# rfid_ctl.net
KiCad netlist of a schematic drawn in EAGLE
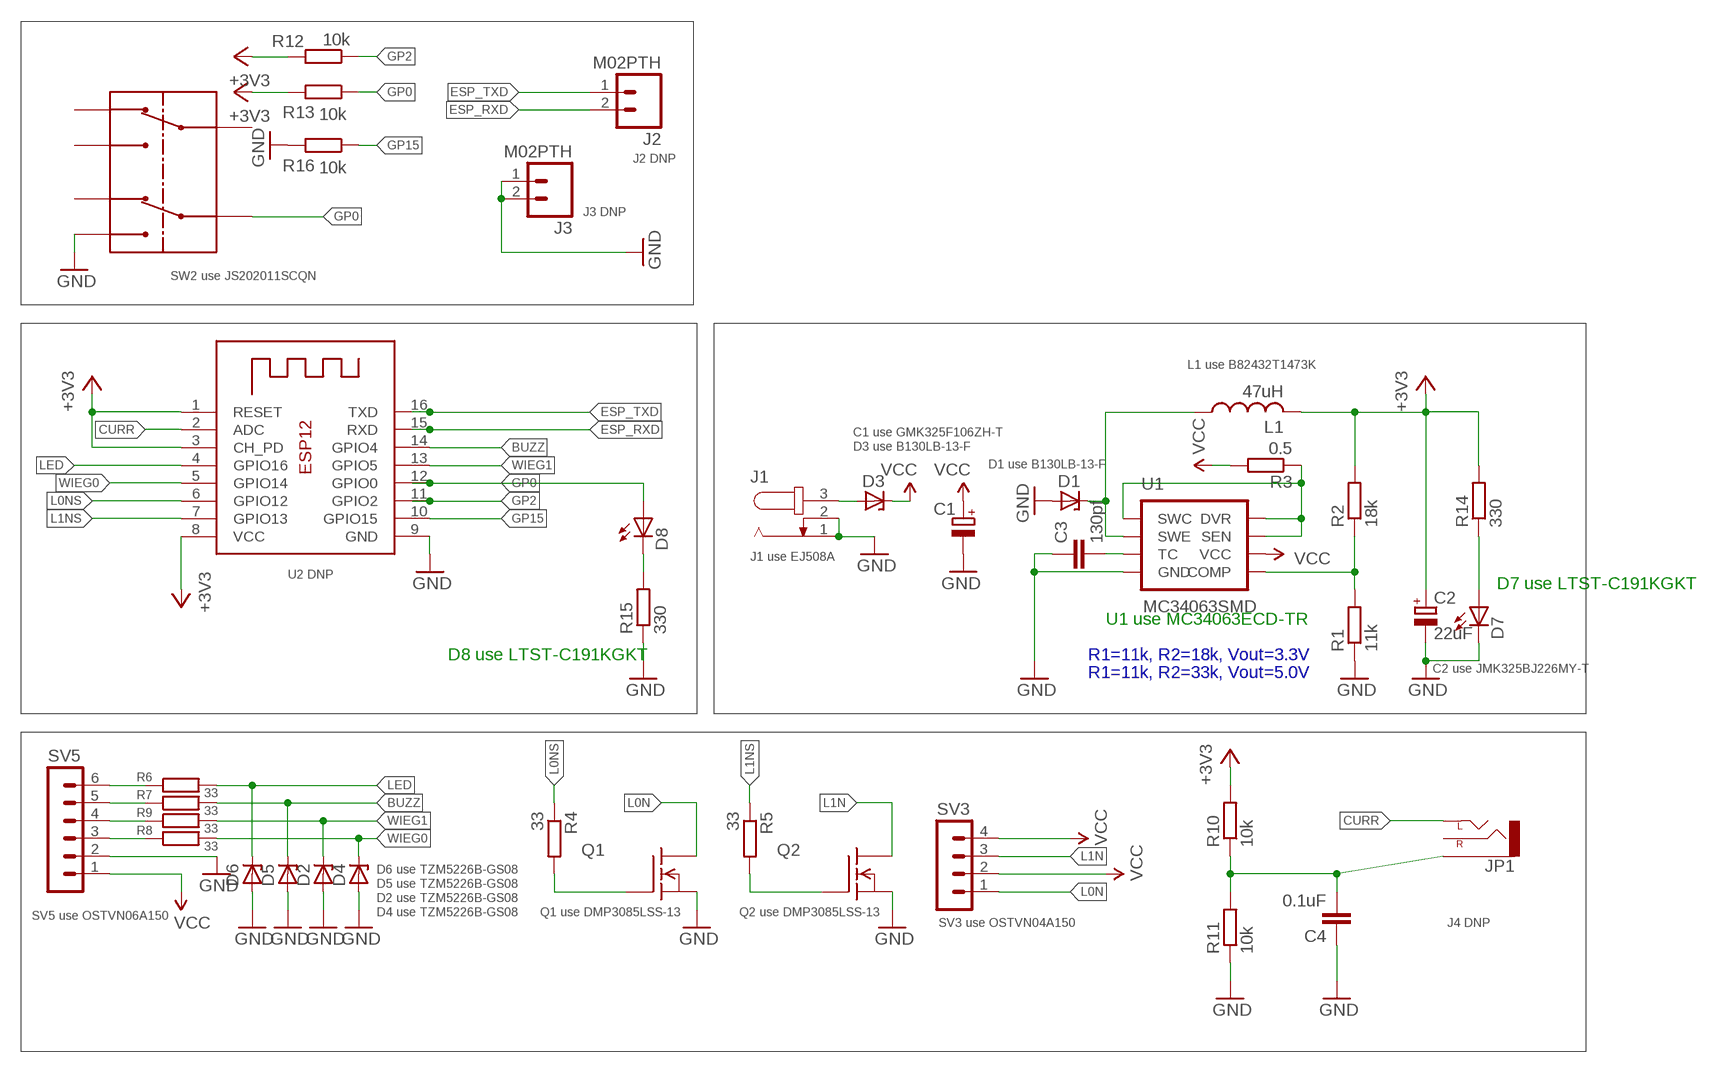
[diagram p0: schematic, sheet 1]

(export (version "E")
  (design (tool "Eeschema 10.0.6"))
  (components
    (comp (ref "C1")
      (value "CPOL-EUB/3528-21R")
      (footprint "eagle-import:B_3528-21R")
      (libsource (lib "eagle-import") (part "CPOL-EUB/3528-21R"))
    )
    (comp (ref "C2")
      (value "22uF")
      (footprint "eagle-import:B_3528-21R")
      (libsource (lib "eagle-import") (part "CPOL-EUB/3528-21R"))
    )
    (comp (ref "C3")
      (value "130pf")
      (footprint "eagle-import:C0603")
      (libsource (lib "eagle-import") (part "C-EUC0603"))
    )
    (comp (ref "C4")
      (value "0.1uF")
      (footprint "eagle-import:C0603")
      (libsource (lib "eagle-import") (part "C-EUC0603"))
    )
    (comp (ref "D1")
      (value "ZENER-DIODESMB")
      (footprint "eagle-import:SMB")
      (libsource (lib "eagle-import") (part "ZENER-DIODESMB"))
    )
    (comp (ref "D2")
      (value "ZENER-DIODESOD80C")
      (footprint "eagle-import:SOD80C")
      (libsource (lib "eagle-import") (part "ZENER-DIODESOD80C"))
    )
    (comp (ref "D3")
      (value "ZENER-DIODESMB")
      (footprint "eagle-import:SMB")
      (libsource (lib "eagle-import") (part "ZENER-DIODESMB"))
    )
    (comp (ref "D4")
      (value "ZENER-DIODESOD80C")
      (footprint "eagle-import:SOD80C")
      (libsource (lib "eagle-import") (part "ZENER-DIODESOD80C"))
    )
    (comp (ref "D5")
      (value "ZENER-DIODESOD80C")
      (footprint "eagle-import:SOD80C")
      (libsource (lib "eagle-import") (part "ZENER-DIODESOD80C"))
    )
    (comp (ref "D6")
      (value "ZENER-DIODESOD80C")
      (footprint "eagle-import:SOD80C")
      (libsource (lib "eagle-import") (part "ZENER-DIODESOD80C"))
    )
    (comp (ref "D7")
      (value "LEDCHIP-LED0603")
      (footprint "eagle-import:CHIP-LED0603")
      (libsource (lib "eagle-import") (part "LEDCHIP-LED0603"))
    )
    (comp (ref "D8")
      (value "LEDCHIP-LED0603")
      (footprint "eagle-import:CHIP-LED0603")
      (libsource (lib "eagle-import") (part "LEDCHIP-LED0603"))
    )
    (comp (ref "J1")
      (value "JACK-PLUG0")
      (footprint "eagle-import:SPC4077")
      (libsource (lib "eagle-import") (part "JACK-PLUG0"))
    )
    (comp (ref "J2")
      (value "M02PTH")
      (footprint "eagle-import:1X02")
      (libsource (lib "eagle-import") (part "M02PTH"))
    )
    (comp (ref "J3")
      (value "M02PTH")
      (footprint "eagle-import:1X02")
      (libsource (lib "eagle-import") (part "M02PTH"))
    )
    (comp (ref "JP1")
      (value "AUDIO-JACKSMD2")
      (footprint "eagle-import:AUDIO-JACK-3.5MM-SMD")
      (libsource (lib "eagle-import") (part "AUDIO-JACKSMD2"))
    )
    (comp (ref "L1")
      (value "47uH")
      (footprint "eagle-import:L1812")
      (libsource (lib "eagle-import") (part "L-USL1812"))
    )
    (comp (ref "Q1")
      (value "FDS5680")
      (footprint "eagle-import:SO-8")
      (libsource (lib "eagle-import") (part "FDS5680"))
    )
    (comp (ref "Q2")
      (value "FDS5680")
      (footprint "eagle-import:SO-8")
      (libsource (lib "eagle-import") (part "FDS5680"))
    )
    (comp (ref "R1")
      (value "11k")
      (footprint "eagle-import:R0603")
      (libsource (lib "eagle-import") (part "R-EU_R0603"))
    )
    (comp (ref "R2")
      (value "18k")
      (footprint "eagle-import:R0603")
      (libsource (lib "eagle-import") (part "R-EU_R0603"))
    )
    (comp (ref "R3")
      (value "0.5")
      (footprint "eagle-import:R0603")
      (libsource (lib "eagle-import") (part "R-EU_R0603"))
    )
    (comp (ref "R4")
      (value "33")
      (footprint "eagle-import:R0603")
      (libsource (lib "eagle-import") (part "R-EU_R0603"))
    )
    (comp (ref "R5")
      (value "33")
      (footprint "eagle-import:R0603")
      (libsource (lib "eagle-import") (part "R-EU_R0603"))
    )
    (comp (ref "R6")
      (value "33")
      (footprint "eagle-import:R0603")
      (libsource (lib "eagle-import") (part "R-EU_R0603"))
    )
    (comp (ref "R7")
      (value "33")
      (footprint "eagle-import:R0603")
      (libsource (lib "eagle-import") (part "R-EU_R0603"))
    )
    (comp (ref "R8")
      (value "33")
      (footprint "eagle-import:R0603")
      (libsource (lib "eagle-import") (part "R-EU_R0603"))
    )
    (comp (ref "R9")
      (value "33")
      (footprint "eagle-import:R0603")
      (libsource (lib "eagle-import") (part "R-EU_R0603"))
    )
    (comp (ref "R10")
      (value "10k")
      (footprint "eagle-import:R0603")
      (libsource (lib "eagle-import") (part "R-EU_R0603"))
    )
    (comp (ref "R11")
      (value "10k")
      (footprint "eagle-import:R0603")
      (libsource (lib "eagle-import") (part "R-EU_R0603"))
    )
    (comp (ref "R12")
      (value "10k")
      (footprint "eagle-import:R0603")
      (libsource (lib "eagle-import") (part "R-EU_R0603"))
    )
    (comp (ref "R13")
      (value "10k")
      (footprint "eagle-import:R0603")
      (libsource (lib "eagle-import") (part "R-EU_R0603"))
    )
    (comp (ref "R14")
      (value "330")
      (footprint "eagle-import:R0603")
      (libsource (lib "eagle-import") (part "R-EU_R0603"))
    )
    (comp (ref "R15")
      (value "330")
      (footprint "eagle-import:R0603")
      (libsource (lib "eagle-import") (part "R-EU_R0603"))
    )
    (comp (ref "R16")
      (value "10k")
      (footprint "eagle-import:R0603")
      (libsource (lib "eagle-import") (part "R-EU_R0603"))
    )
    (comp (ref "SV3")
      (value "MA04-1")
      (footprint "eagle-import:MA04-1")
      (libsource (lib "eagle-import") (part "MA04-1"))
    )
    (comp (ref "SV5")
      (value "MA06-1")
      (footprint "eagle-import:MA06-1")
      (libsource (lib "eagle-import") (part "MA06-1"))
    )
    (comp (ref "SW2")
      (value "L202011MS02Q")
      (footprint "eagle-import:SMT")
      (libsource (lib "eagle-import") (part "L202011MS02Q"))
    )
    (comp (ref "U1")
      (value "MC34063SMD")
      (footprint "eagle-import:SO08")
      (libsource (lib "eagle-import") (part "MC34063SMD"))
    )
    (comp (ref "U2")
      (value "ESP-12")
      (footprint "eagle-import:ESP-12")
      (libsource (lib "eagle-import") (part "ESP-12"))
    )
  )
  (nets
    (net (code "1") (name "+3V3") (class "Default")
      (node (ref "C2") (pin "+") (pinfunction "+_+") (pintype "passive"))
      (node (ref "L1") (pin "2") (pinfunction "2_2") (pintype "passive"))
      (node (ref "R10") (pin "2") (pinfunction "2_2") (pintype "passive"))
      (node (ref "R12") (pin "2") (pinfunction "2_2") (pintype "passive"))
      (node (ref "R13") (pin "2") (pinfunction "2_2") (pintype "passive"))
      (node (ref "R14") (pin "2") (pinfunction "2_2") (pintype "passive"))
      (node (ref "R2") (pin "2") (pinfunction "2_2") (pintype "passive"))
      (node (ref "U2") (pin "1") (pinfunction "RESET_1") (pintype "input"))
      (node (ref "U2") (pin "3") (pinfunction "CH_PD_3") (pintype "input"))
      (node (ref "U2") (pin "8") (pinfunction "VCC_8") (pintype "power_in"))
    )
    (net (code "2") (name "BUZZ") (class "Default")
      (node (ref "D5") (pin "C") (pinfunction "C_C") (pintype "passive"))
      (node (ref "R7") (pin "2") (pinfunction "2_2") (pintype "passive"))
      (node (ref "U2") (pin "14") (pinfunction "GPIO4_14") (pintype "bidirectional"))
    )
    (net (code "3") (name "CURR") (class "Default")
      (node (ref "JP1") (pin "TIP") (pinfunction "LEFT_TIP") (pintype "bidirectional"))
      (node (ref "U2") (pin "2") (pinfunction "ADC_2") (pintype "passive"))
    )
    (net (code "4") (name "ESP_RXD") (class "Default")
      (node (ref "J2") (pin "2") (pinfunction "2_2") (pintype "passive"))
      (node (ref "U2") (pin "15") (pinfunction "RXD_15") (pintype "input"))
    )
    (net (code "5") (name "ESP_TXD") (class "Default")
      (node (ref "J2") (pin "1") (pinfunction "1_1") (pintype "passive"))
      (node (ref "U2") (pin "16") (pinfunction "TXD_16") (pintype "output"))
    )
    (net (code "6") (name "GND") (class "Default")
      (node (ref "C1") (pin "-") (pinfunction "-_-") (pintype "passive"))
      (node (ref "C2") (pin "-") (pinfunction "-_-") (pintype "passive"))
      (node (ref "C3") (pin "1") (pinfunction "1_1") (pintype "passive"))
      (node (ref "C4") (pin "1") (pinfunction "1_1") (pintype "passive"))
      (node (ref "D1") (pin "A") (pinfunction "A_A") (pintype "passive"))
      (node (ref "D2") (pin "A") (pinfunction "A_A") (pintype "passive"))
      (node (ref "D4") (pin "A") (pinfunction "A_A") (pintype "passive"))
      (node (ref "D5") (pin "A") (pinfunction "A_A") (pintype "passive"))
      (node (ref "D6") (pin "A") (pinfunction "A_A") (pintype "passive"))
      (node (ref "D7") (pin "C") (pinfunction "C_C") (pintype "passive"))
      (node (ref "J1") (pin "1") (pinfunction "1_1") (pintype "passive"))
      (node (ref "J1") (pin "2") (pinfunction "2_2") (pintype "passive"))
      (node (ref "J3") (pin "1") (pinfunction "1_1") (pintype "passive"))
      (node (ref "J3") (pin "2") (pinfunction "2_2") (pintype "passive"))
      (node (ref "Q1") (pin "1") (pinfunction "S_1") (pintype "passive"))
      (node (ref "Q1") (pin "2") (pinfunction "S_2") (pintype "passive"))
      (node (ref "Q1") (pin "3") (pinfunction "S_3") (pintype "passive"))
      (node (ref "Q2") (pin "1") (pinfunction "S_1") (pintype "passive"))
      (node (ref "Q2") (pin "2") (pinfunction "S_2") (pintype "passive"))
      (node (ref "Q2") (pin "3") (pinfunction "S_3") (pintype "passive"))
      (node (ref "R1") (pin "1") (pinfunction "1_1") (pintype "passive"))
      (node (ref "R11") (pin "1") (pinfunction "1_1") (pintype "passive"))
      (node (ref "R15") (pin "1") (pinfunction "1_1") (pintype "passive"))
      (node (ref "R16") (pin "2") (pinfunction "2_2") (pintype "passive"))
      (node (ref "SV5") (pin "2") (pinfunction "2_2") (pintype "passive"))
      (node (ref "SW2") (pin "B1") (pinfunction "B1_B1") (pintype "bidirectional"))
      (node (ref "U1") (pin "4") (pinfunction "GND_4") (pintype "bidirectional"))
      (node (ref "U2") (pin "9") (pinfunction "GND_9") (pintype "power_in"))
    )
    (net (code "7") (name "GP0") (class "Default")
      (node (ref "D8") (pin "A") (pinfunction "A_A") (pintype "passive"))
      (node (ref "R13") (pin "1") (pinfunction "1_1") (pintype "passive"))
      (node (ref "SW2") (pin "B") (pinfunction "B_B") (pintype "bidirectional"))
      (node (ref "U2") (pin "12") (pinfunction "GPIO0_12") (pintype "bidirectional"))
    )
    (net (code "8") (name "GP2") (class "Default")
      (node (ref "R12") (pin "1") (pinfunction "1_1") (pintype "passive"))
      (node (ref "U2") (pin "11") (pinfunction "GPIO2_11") (pintype "bidirectional"))
    )
    (net (code "9") (name "GP15") (class "Default")
      (node (ref "R16") (pin "1") (pinfunction "1_1") (pintype "passive"))
      (node (ref "U2") (pin "10") (pinfunction "GPIO15_10") (pintype "bidirectional"))
    )
    (net (code "10") (name "L0N") (class "Default")
      (node (ref "Q1") (pin "5") (pinfunction "D_5") (pintype "passive"))
      (node (ref "Q1") (pin "6") (pinfunction "D_6") (pintype "passive"))
      (node (ref "Q1") (pin "7") (pinfunction "D_7") (pintype "passive"))
      (node (ref "Q1") (pin "8") (pinfunction "D_8") (pintype "passive"))
      (node (ref "SV3") (pin "1") (pinfunction "1_1") (pintype "passive"))
    )
    (net (code "11") (name "L0NS") (class "Default")
      (node (ref "R4") (pin "1") (pinfunction "1_1") (pintype "passive"))
      (node (ref "U2") (pin "6") (pinfunction "GPIO12_6") (pintype "bidirectional"))
    )
    (net (code "12") (name "L1N") (class "Default")
      (node (ref "Q2") (pin "5") (pinfunction "D_5") (pintype "passive"))
      (node (ref "Q2") (pin "6") (pinfunction "D_6") (pintype "passive"))
      (node (ref "Q2") (pin "7") (pinfunction "D_7") (pintype "passive"))
      (node (ref "Q2") (pin "8") (pinfunction "D_8") (pintype "passive"))
      (node (ref "SV3") (pin "3") (pinfunction "3_3") (pintype "passive"))
    )
    (net (code "13") (name "L1NS") (class "Default")
      (node (ref "R5") (pin "1") (pinfunction "1_1") (pintype "passive"))
      (node (ref "U2") (pin "7") (pinfunction "GPIO13_7") (pintype "bidirectional"))
    )
    (net (code "14") (name "LED") (class "Default")
      (node (ref "D6") (pin "C") (pinfunction "C_C") (pintype "passive"))
      (node (ref "R6") (pin "2") (pinfunction "2_2") (pintype "passive"))
      (node (ref "U2") (pin "4") (pinfunction "GPIO16_4") (pintype "bidirectional"))
    )
    (net (code "15") (name "Net-(C4-Pad2)") (class "Default")
      (node (ref "C4") (pin "2") (pinfunction "2_2") (pintype "passive"))
      (node (ref "JP1") (pin "SLEEVE") (pinfunction "SLEEVE_SLEEVE") (pintype "bidirectional"))
      (node (ref "R10") (pin "1") (pinfunction "1_1") (pintype "passive"))
      (node (ref "R11") (pin "2") (pinfunction "2_2") (pintype "passive"))
    )
    (net (code "16") (name "Net-(D3-PadA)") (class "Default")
      (node (ref "D3") (pin "A") (pinfunction "A_A") (pintype "passive"))
      (node (ref "J1") (pin "3") (pinfunction "3_3") (pintype "passive"))
    )
    (net (code "17") (name "Net-(D7-PadA)") (class "Default")
      (node (ref "D7") (pin "A") (pinfunction "A_A") (pintype "passive"))
      (node (ref "R14") (pin "1") (pinfunction "1_1") (pintype "passive"))
    )
    (net (code "18") (name "Net-(D8-PadC)") (class "Default")
      (node (ref "D8") (pin "C") (pinfunction "C_C") (pintype "passive"))
      (node (ref "R15") (pin "2") (pinfunction "2_2") (pintype "passive"))
    )
    (net (code "19") (name "Net-(Q1-G)") (class "Default")
      (node (ref "Q1") (pin "4") (pinfunction "G_4") (pintype "passive"))
      (node (ref "R4") (pin "2") (pinfunction "2_2") (pintype "passive"))
    )
    (net (code "20") (name "Net-(Q2-G)") (class "Default")
      (node (ref "Q2") (pin "4") (pinfunction "G_4") (pintype "passive"))
      (node (ref "R5") (pin "2") (pinfunction "2_2") (pintype "passive"))
    )
    (net (code "21") (name "Net-(R6-Pad1)") (class "Default")
      (node (ref "R6") (pin "1") (pinfunction "1_1") (pintype "passive"))
      (node (ref "SV5") (pin "6") (pinfunction "6_6") (pintype "passive"))
    )
    (net (code "22") (name "Net-(R7-Pad1)") (class "Default")
      (node (ref "R7") (pin "1") (pinfunction "1_1") (pintype "passive"))
      (node (ref "SV5") (pin "5") (pinfunction "5_5") (pintype "passive"))
    )
    (net (code "23") (name "Net-(R8-Pad1)") (class "Default")
      (node (ref "R8") (pin "1") (pinfunction "1_1") (pintype "passive"))
      (node (ref "SV5") (pin "4") (pinfunction "4_4") (pintype "passive"))
    )
    (net (code "24") (name "Net-(R9-Pad1)") (class "Default")
      (node (ref "R9") (pin "1") (pinfunction "1_1") (pintype "passive"))
      (node (ref "SV5") (pin "3") (pinfunction "3_3") (pintype "passive"))
    )
    (net (code "25") (name "Net-(U1-COMP)") (class "Default")
      (node (ref "R1") (pin "2") (pinfunction "2_2") (pintype "passive"))
      (node (ref "R2") (pin "1") (pinfunction "1_1") (pintype "passive"))
      (node (ref "U1") (pin "5") (pinfunction "COMP_5") (pintype "bidirectional"))
    )
    (net (code "26") (name "Net-(U1-DVR)") (class "Default")
      (node (ref "R3") (pin "1") (pinfunction "1_1") (pintype "passive"))
      (node (ref "U1") (pin "1") (pinfunction "SWC_1") (pintype "bidirectional"))
      (node (ref "U1") (pin "7") (pinfunction "SEN_7") (pintype "bidirectional"))
      (node (ref "U1") (pin "8") (pinfunction "DVR_8") (pintype "bidirectional"))
    )
    (net (code "27") (name "Net-(U1-SWE)") (class "Default")
      (node (ref "D1") (pin "C") (pinfunction "C_C") (pintype "passive"))
      (node (ref "L1") (pin "1") (pinfunction "1_1") (pintype "passive"))
      (node (ref "U1") (pin "2") (pinfunction "SWE_2") (pintype "bidirectional"))
    )
    (net (code "28") (name "Net-(U1-TC)") (class "Default")
      (node (ref "C3") (pin "2") (pinfunction "2_2") (pintype "passive"))
      (node (ref "U1") (pin "3") (pinfunction "TC_3") (pintype "bidirectional"))
    )
    (net (code "29") (name "VCC") (class "Default")
      (node (ref "C1") (pin "+") (pinfunction "+_+") (pintype "passive"))
      (node (ref "D3") (pin "C") (pinfunction "C_C") (pintype "passive"))
      (node (ref "R3") (pin "2") (pinfunction "2_2") (pintype "passive"))
      (node (ref "SV3") (pin "2") (pinfunction "2_2") (pintype "passive"))
      (node (ref "SV3") (pin "4") (pinfunction "4_4") (pintype "passive"))
      (node (ref "SV5") (pin "1") (pinfunction "1_1") (pintype "passive"))
      (node (ref "U1") (pin "6") (pinfunction "VCC_6") (pintype "bidirectional"))
    )
    (net (code "30") (name "WIEG0") (class "Default")
      (node (ref "D4") (pin "C") (pinfunction "C_C") (pintype "passive"))
      (node (ref "R9") (pin "2") (pinfunction "2_2") (pintype "passive"))
      (node (ref "U2") (pin "5") (pinfunction "GPIO14_5") (pintype "bidirectional"))
    )
    (net (code "31") (name "WIEG1") (class "Default")
      (node (ref "D2") (pin "C") (pinfunction "C_C") (pintype "passive"))
      (node (ref "R8") (pin "2") (pinfunction "2_2") (pintype "passive"))
      (node (ref "U2") (pin "13") (pinfunction "GPIO5_13") (pintype "bidirectional"))
    )
    (net (code "32") (name "unconnected-(JP1-RIGHT-PadRING)") (class "Default")
      (node (ref "JP1") (pin "RING") (pinfunction "RIGHT_RING") (pintype "bidirectional"))
    )
    (net (code "33") (name "unconnected-(SW2-PadA)") (class "Default")
      (node (ref "SW2") (pin "A") (pinfunction "A_A") (pintype "bidirectional"))
    )
    (net (code "34") (name "unconnected-(SW2-PadA1)") (class "Default")
      (node (ref "SW2") (pin "A1") (pinfunction "A1_A1") (pintype "bidirectional"))
    )
    (net (code "35") (name "unconnected-(SW2-PadA2)") (class "Default")
      (node (ref "SW2") (pin "A2") (pinfunction "A2_A2") (pintype "bidirectional"))
    )
    (net (code "36") (name "unconnected-(SW2-PadB2)") (class "Default")
      (node (ref "SW2") (pin "B2") (pinfunction "B2_B2") (pintype "bidirectional"))
    )
  )
)
